# isoSPI_block.net
KiCad netlist of a schematic drawn in Altium Designer
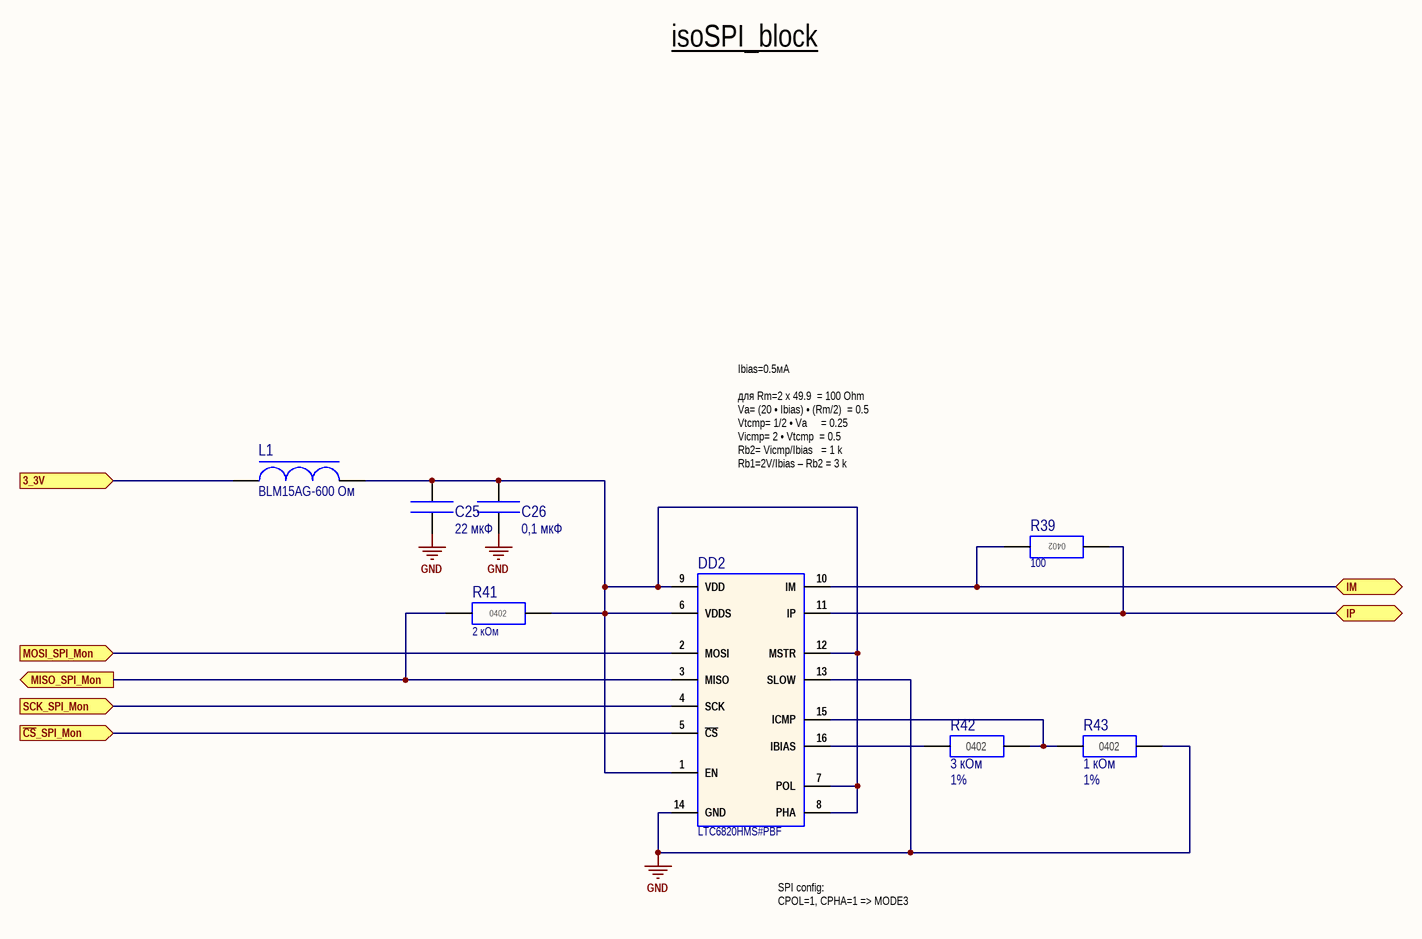
[diagram p0: isoSPI_block.SchDoc]

(export (version "E")
  (design (tool "Eeschema 10.0.6"))
  (components
    (comp (ref "C25")
      (value "22 мкФ")
      (footprint "CC1206")
      (description "Чип конденсатор керамический")
      (fields (field (name "Comment") "CC1206-X7R-22 мкФ-20%-100В"))
      (libsource (lib "Конденсаторы") (part "CC1206-X7R-#-20%-100В"))
    )
    (comp (ref "C26")
      (value "0,1 мкФ")
      (footprint "CC0402(1005)")
      (description "Чип конденсатор керамический")
      (fields (field (name "Comment") "CC0402-X7R-0,1 мкФ-20%-50В"))
      (libsource (lib "Конденсаторы") (part "CC0402-X7R-#-20%-50В"))
    )
    (comp (ref "DD2")
      (value "LTC6820HMS#PBF")
      (footprint "MSOP-16_MS")
      (description "isoSPI Isolated Communications Interface")
      (fields (field (name "MANUFACTURER_PART_NUMBER") "ltc6820hms#pbf"))
      (libsource (lib "batmon_ICs") (part "LTC6820HMS#PBF"))
    )
    (comp (ref "L1")
      (value "BLM15AG-600 Ом")
      (footprint "CL0402(1005)")
      (description "Чип индуктивность подавления EMP")
      (libsource (lib "Индуктивности") (part "BLM15"))
    )
    (comp (ref "R39")
      (value "100")
      (footprint "CR0402(1005)")
      (description "Чип резистор")
      (fields (field (name "TOLERANCE") "5%") (field (name "Comment") "CR0402-100-±5%"))
      (libsource (lib "Чип резисторы_small") (part "CR0402-#-±5%"))
    )
    (comp (ref "R41")
      (value "2 кОм")
      (footprint "CR0402(1005)")
      (description "Чип резистор")
      (fields (field (name "TOLERANCE") "5%") (field (name "Comment") "CR0402-2 кОм-±5%"))
      (libsource (lib "Резисторы") (part "CR0402-#-±5%"))
    )
    (comp (ref "R42")
      (value "3 кОм")
      (footprint "CR0402(1005)")
      (description "Чип резистор")
      (fields (field (name "TOLERANCE") "1%") (field (name "Comment") "CR0402-3 кОм-±1%"))
      (libsource (lib "Резисторы") (part "CR0402-#-±1%"))
    )
    (comp (ref "R43")
      (value "1 кОм")
      (footprint "CR0402(1005)")
      (description "Чип резистор")
      (fields (field (name "TOLERANCE") "1%") (field (name "Comment") "CR0402-1 кОм-±1%"))
      (libsource (lib "Резисторы") (part "CR0402-#-±1%"))
    )
  )
  (nets
    (net (code "1") (name "/3_3V") (class "Default")
      (node (ref "L1") (pin "1") (pinfunction "1_1") (pintype "passive"))
    )
    (net (code "2") (name "/IM") (class "Default")
      (node (ref "DD2") (pin "10") (pinfunction "IM_10") (pintype "passive"))
      (node (ref "R39") (pin "2") (pinfunction "-_2") (pintype "passive"))
    )
    (net (code "3") (name "/IP") (class "Default")
      (node (ref "DD2") (pin "11") (pinfunction "IP_11") (pintype "passive"))
      (node (ref "R39") (pin "1") (pinfunction "+_1") (pintype "passive"))
    )
    (net (code "4") (name "/MISO_SPI_Mon") (class "Default")
      (node (ref "DD2") (pin "3") (pinfunction "MISO_3") (pintype "passive"))
      (node (ref "R41") (pin "1") (pinfunction "+_1") (pintype "passive"))
    )
    (net (code "5") (name "/MOSI_SPI_Mon") (class "Default")
      (node (ref "DD2") (pin "2") (pinfunction "MOSI_2") (pintype "passive"))
    )
    (net (code "6") (name "/SCK_SPI_Mon") (class "Default")
      (node (ref "DD2") (pin "4") (pinfunction "SCK_4") (pintype "passive"))
    )
    (net (code "7") (name "/~{CS}_SPI_Mon") (class "Default")
      (node (ref "DD2") (pin "5") (pinfunction "~{CS}_5") (pintype "passive"))
    )
    (net (code "8") (name "GND") (class "Default")
      (node (ref "C25") (pin "2") (pinfunction "-_2") (pintype "passive"))
      (node (ref "C26") (pin "2") (pinfunction "-_2") (pintype "passive"))
      (node (ref "DD2") (pin "13") (pinfunction "SLOW_13") (pintype "passive"))
      (node (ref "DD2") (pin "14") (pinfunction "GND_14") (pintype "power_in"))
      (node (ref "R43") (pin "2") (pinfunction "-_2") (pintype "passive"))
    )
    (net (code "9") (name "Net-(C25-+)") (class "Default")
      (node (ref "C25") (pin "1") (pinfunction "+_1") (pintype "passive"))
      (node (ref "C26") (pin "1") (pinfunction "+_1") (pintype "passive"))
      (node (ref "DD2") (pin "1") (pinfunction "EN_1") (pintype "passive"))
      (node (ref "DD2") (pin "12") (pinfunction "MSTR_12") (pintype "passive"))
      (node (ref "DD2") (pin "6") (pinfunction "VDDS_6") (pintype "power_in"))
      (node (ref "DD2") (pin "7") (pinfunction "POL_7") (pintype "passive"))
      (node (ref "DD2") (pin "8") (pinfunction "PHA_8") (pintype "passive"))
      (node (ref "DD2") (pin "9") (pinfunction "VDD_9") (pintype "power_in"))
      (node (ref "L1") (pin "2") (pinfunction "2_2") (pintype "passive"))
      (node (ref "R41") (pin "2") (pinfunction "-_2") (pintype "passive"))
    )
    (net (code "10") (name "Net-(DD2-IBIAS)") (class "Default")
      (node (ref "DD2") (pin "16") (pinfunction "IBIAS_16") (pintype "passive"))
      (node (ref "R42") (pin "1") (pinfunction "+_1") (pintype "passive"))
    )
    (net (code "11") (name "Net-(DD2-ICMP)") (class "Default")
      (node (ref "DD2") (pin "15") (pinfunction "ICMP_15") (pintype "passive"))
      (node (ref "R42") (pin "2") (pinfunction "-_2") (pintype "passive"))
      (node (ref "R43") (pin "1") (pinfunction "+_1") (pintype "passive"))
    )
  )
)
